# Convertidor4bits.net
KiCad netlist of a schematic drawn in EAGLE
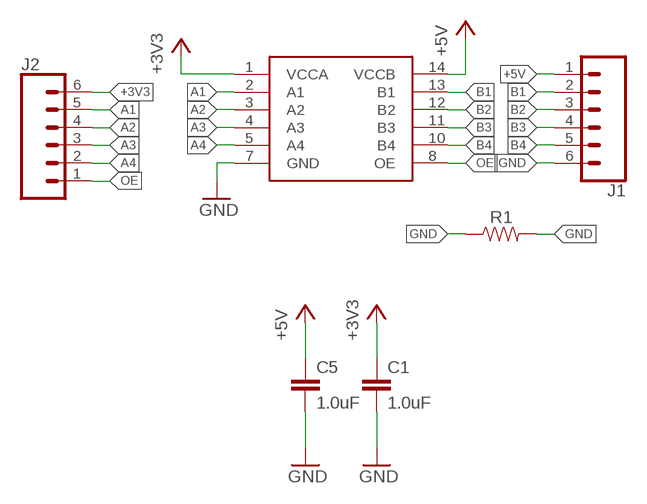
[diagram p0: schematic, sheet 1]

(export (version "E")
  (design (tool "Eeschema 10.0.6"))
  (components
    (comp (ref "C1")
      (value "1.0uF")
      (footprint "eagle-import:0805")
      (libsource (lib "eagle-import") (part "1.0UF-0805-25V-(+80/-20%)"))
    )
    (comp (ref "C5")
      (value "1.0uF")
      (footprint "eagle-import:0805")
      (libsource (lib "eagle-import") (part "1.0UF-0805-25V-(+80/-20%)"))
    )
    (comp (ref "IC1")
      (value "TXB0104")
      (footprint "eagle-import:SO14")
      (libsource (lib "eagle-import") (part "TXB0104"))
    )
    (comp (ref "J1")
      (value "CONN_06LONGPADS")
      (footprint "eagle-import:1X06_LONGPADS")
      (libsource (lib "eagle-import") (part "CONN_06LONGPADS"))
    )
    (comp (ref "J2")
      (value "CONN_06LONGPADS")
      (footprint "eagle-import:1X06_LONGPADS")
      (libsource (lib "eagle-import") (part "CONN_06LONGPADS"))
    )
    (comp (ref "R1")
      (value "RESISTOR0805")
      (footprint "eagle-import:0805")
      (libsource (lib "eagle-import") (part "RESISTOR0805"))
    )
  )
  (nets
    (net (code "1") (name "+3V3") (class "Default")
      (node (ref "C1") (pin "1") (pinfunction "1_1") (pintype "passive"))
      (node (ref "IC1") (pin "1") (pinfunction "VCCA_1") (pintype "power_in"))
      (node (ref "J2") (pin "6") (pinfunction "6_6") (pintype "passive"))
    )
    (net (code "2") (name "+5V") (class "Default")
      (node (ref "C5") (pin "1") (pinfunction "1_1") (pintype "passive"))
      (node (ref "IC1") (pin "14") (pinfunction "VCCB_14") (pintype "power_in"))
      (node (ref "J1") (pin "1") (pinfunction "1_1") (pintype "passive"))
    )
    (net (code "3") (name "A1") (class "Default")
      (node (ref "IC1") (pin "2") (pinfunction "A1_2") (pintype "bidirectional"))
      (node (ref "J2") (pin "5") (pinfunction "5_5") (pintype "passive"))
    )
    (net (code "4") (name "A2") (class "Default")
      (node (ref "IC1") (pin "3") (pinfunction "A2_3") (pintype "bidirectional"))
      (node (ref "J2") (pin "4") (pinfunction "4_4") (pintype "passive"))
    )
    (net (code "5") (name "A3") (class "Default")
      (node (ref "IC1") (pin "4") (pinfunction "A3_4") (pintype "bidirectional"))
      (node (ref "J2") (pin "3") (pinfunction "3_3") (pintype "passive"))
    )
    (net (code "6") (name "A4") (class "Default")
      (node (ref "IC1") (pin "5") (pinfunction "A4_5") (pintype "bidirectional"))
      (node (ref "J2") (pin "2") (pinfunction "2_2") (pintype "passive"))
    )
    (net (code "7") (name "B1") (class "Default")
      (node (ref "IC1") (pin "13") (pinfunction "B1_13") (pintype "bidirectional"))
      (node (ref "J1") (pin "2") (pinfunction "2_2") (pintype "passive"))
    )
    (net (code "8") (name "B2") (class "Default")
      (node (ref "IC1") (pin "12") (pinfunction "B2_12") (pintype "bidirectional"))
      (node (ref "J1") (pin "3") (pinfunction "3_3") (pintype "passive"))
    )
    (net (code "9") (name "B3") (class "Default")
      (node (ref "IC1") (pin "11") (pinfunction "B3_11") (pintype "bidirectional"))
      (node (ref "J1") (pin "4") (pinfunction "4_4") (pintype "passive"))
    )
    (net (code "10") (name "B4") (class "Default")
      (node (ref "IC1") (pin "10") (pinfunction "B4_10") (pintype "bidirectional"))
      (node (ref "J1") (pin "5") (pinfunction "5_5") (pintype "passive"))
    )
    (net (code "11") (name "GND") (class "Default")
      (node (ref "C1") (pin "2") (pinfunction "2_2") (pintype "passive"))
      (node (ref "C5") (pin "2") (pinfunction "2_2") (pintype "passive"))
      (node (ref "IC1") (pin "7") (pinfunction "GND_7") (pintype "power_in"))
      (node (ref "J1") (pin "6") (pinfunction "6_6") (pintype "passive"))
      (node (ref "R1") (pin "1") (pinfunction "1_1") (pintype "passive"))
      (node (ref "R1") (pin "2") (pinfunction "2_2") (pintype "passive"))
    )
    (net (code "12") (name "OE") (class "Default")
      (node (ref "IC1") (pin "8") (pinfunction "OE_8") (pintype "input"))
      (node (ref "J2") (pin "1") (pinfunction "1_1") (pintype "passive"))
    )
  )
)
